# Ears_0603.net
KiCad netlist of a schematic drawn in EAGLE
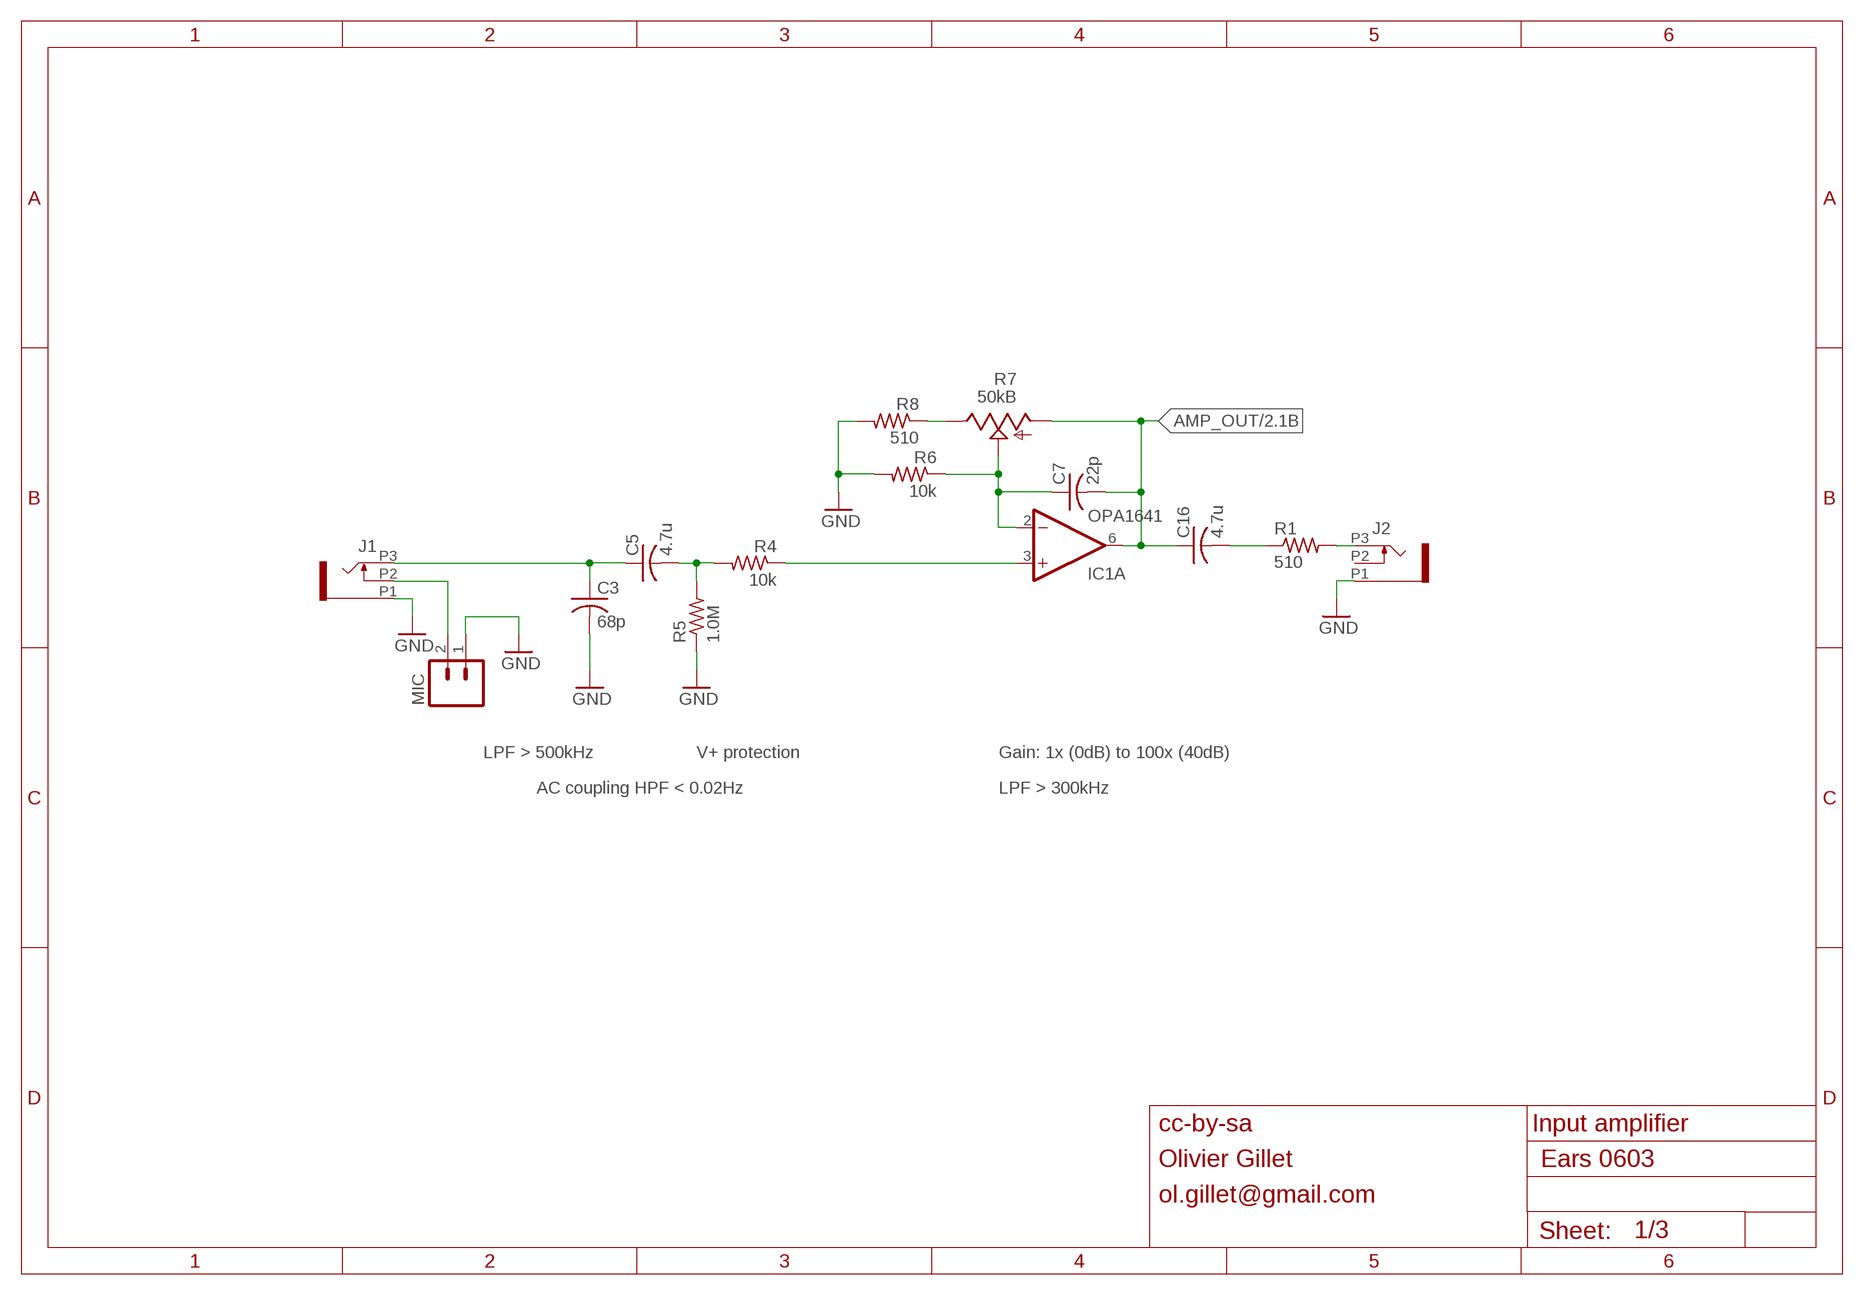
[diagram p0: schematic, sheet 1]
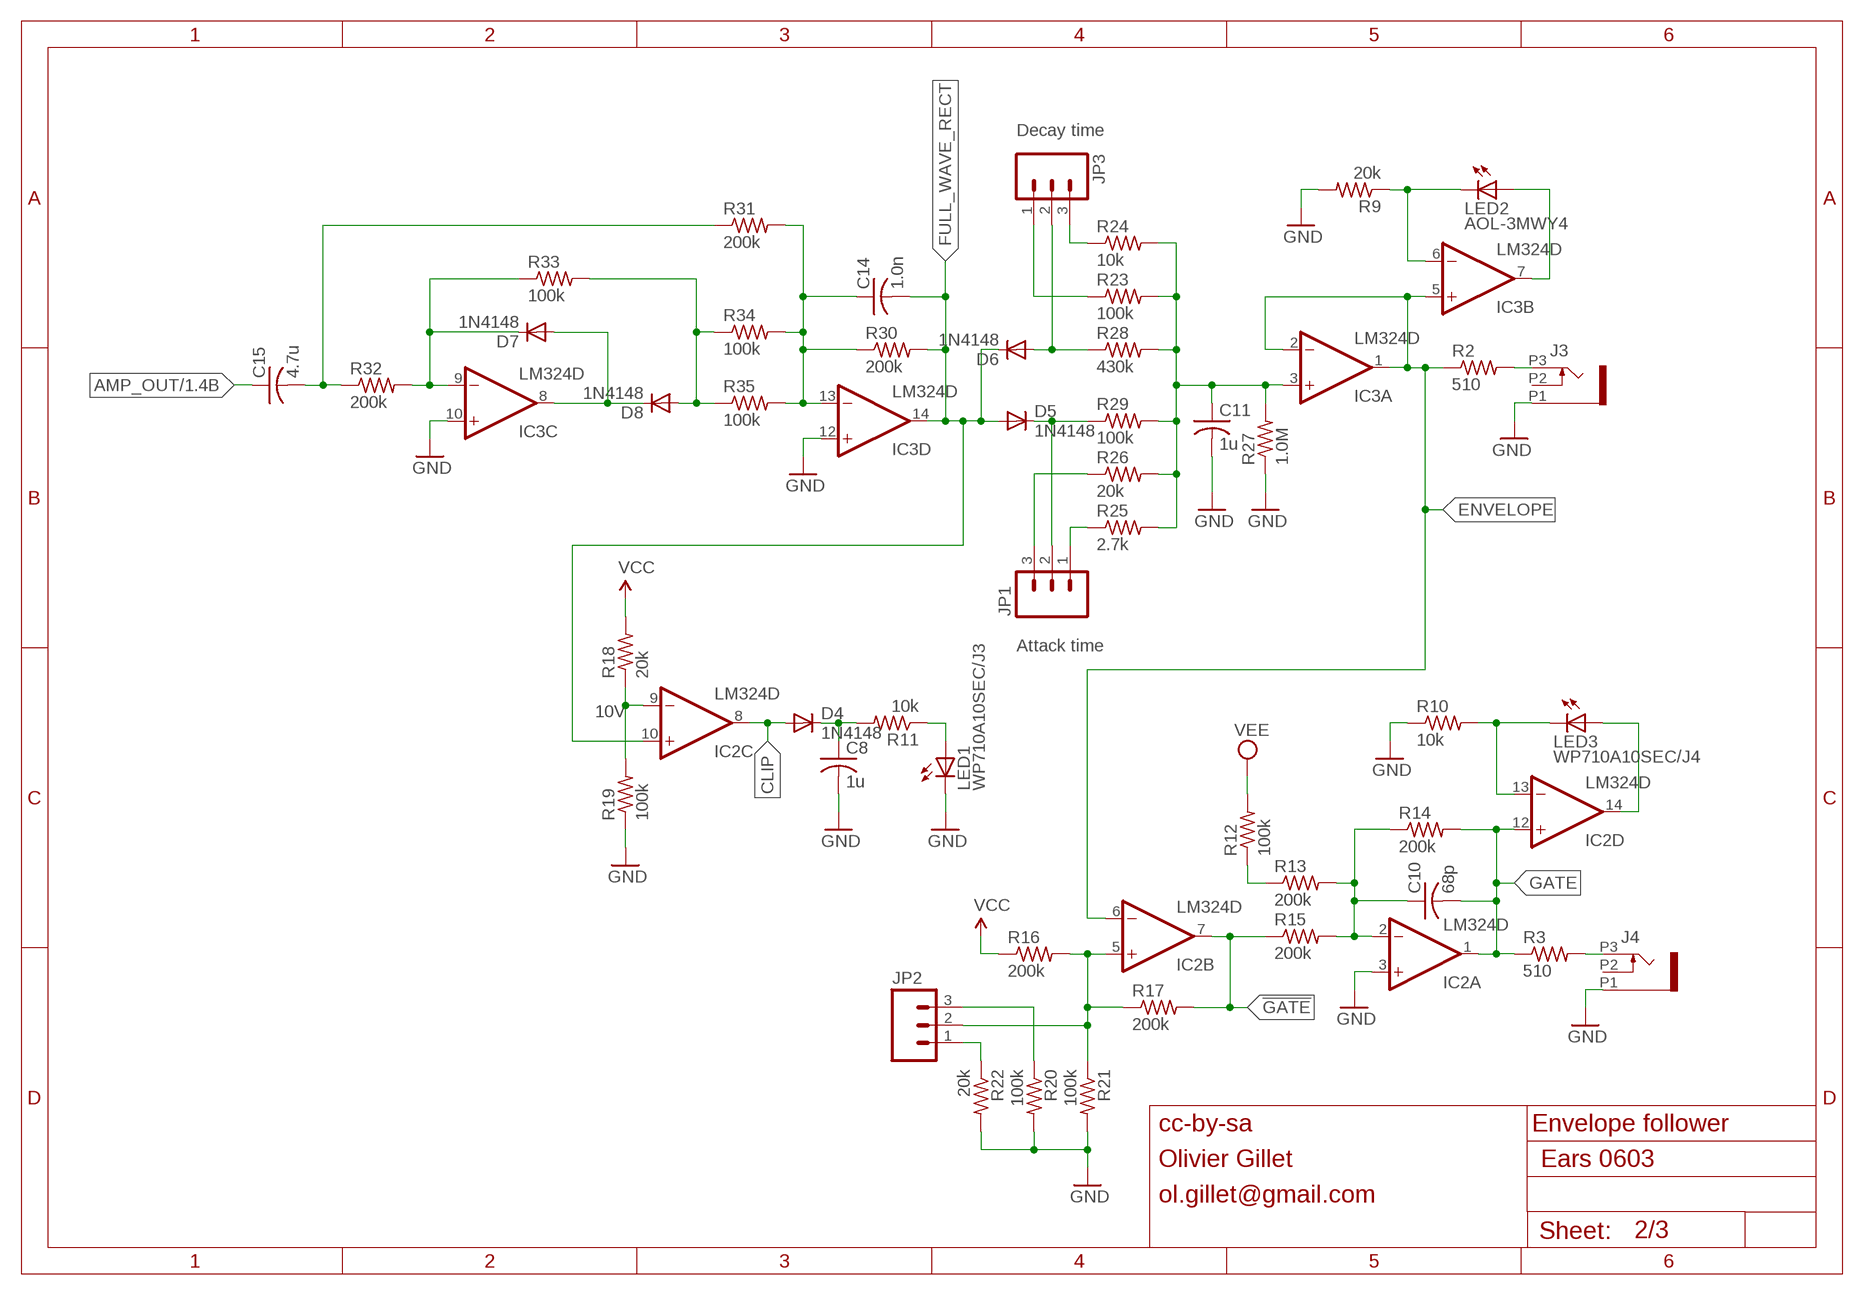
[diagram p1: schematic, sheet 2]
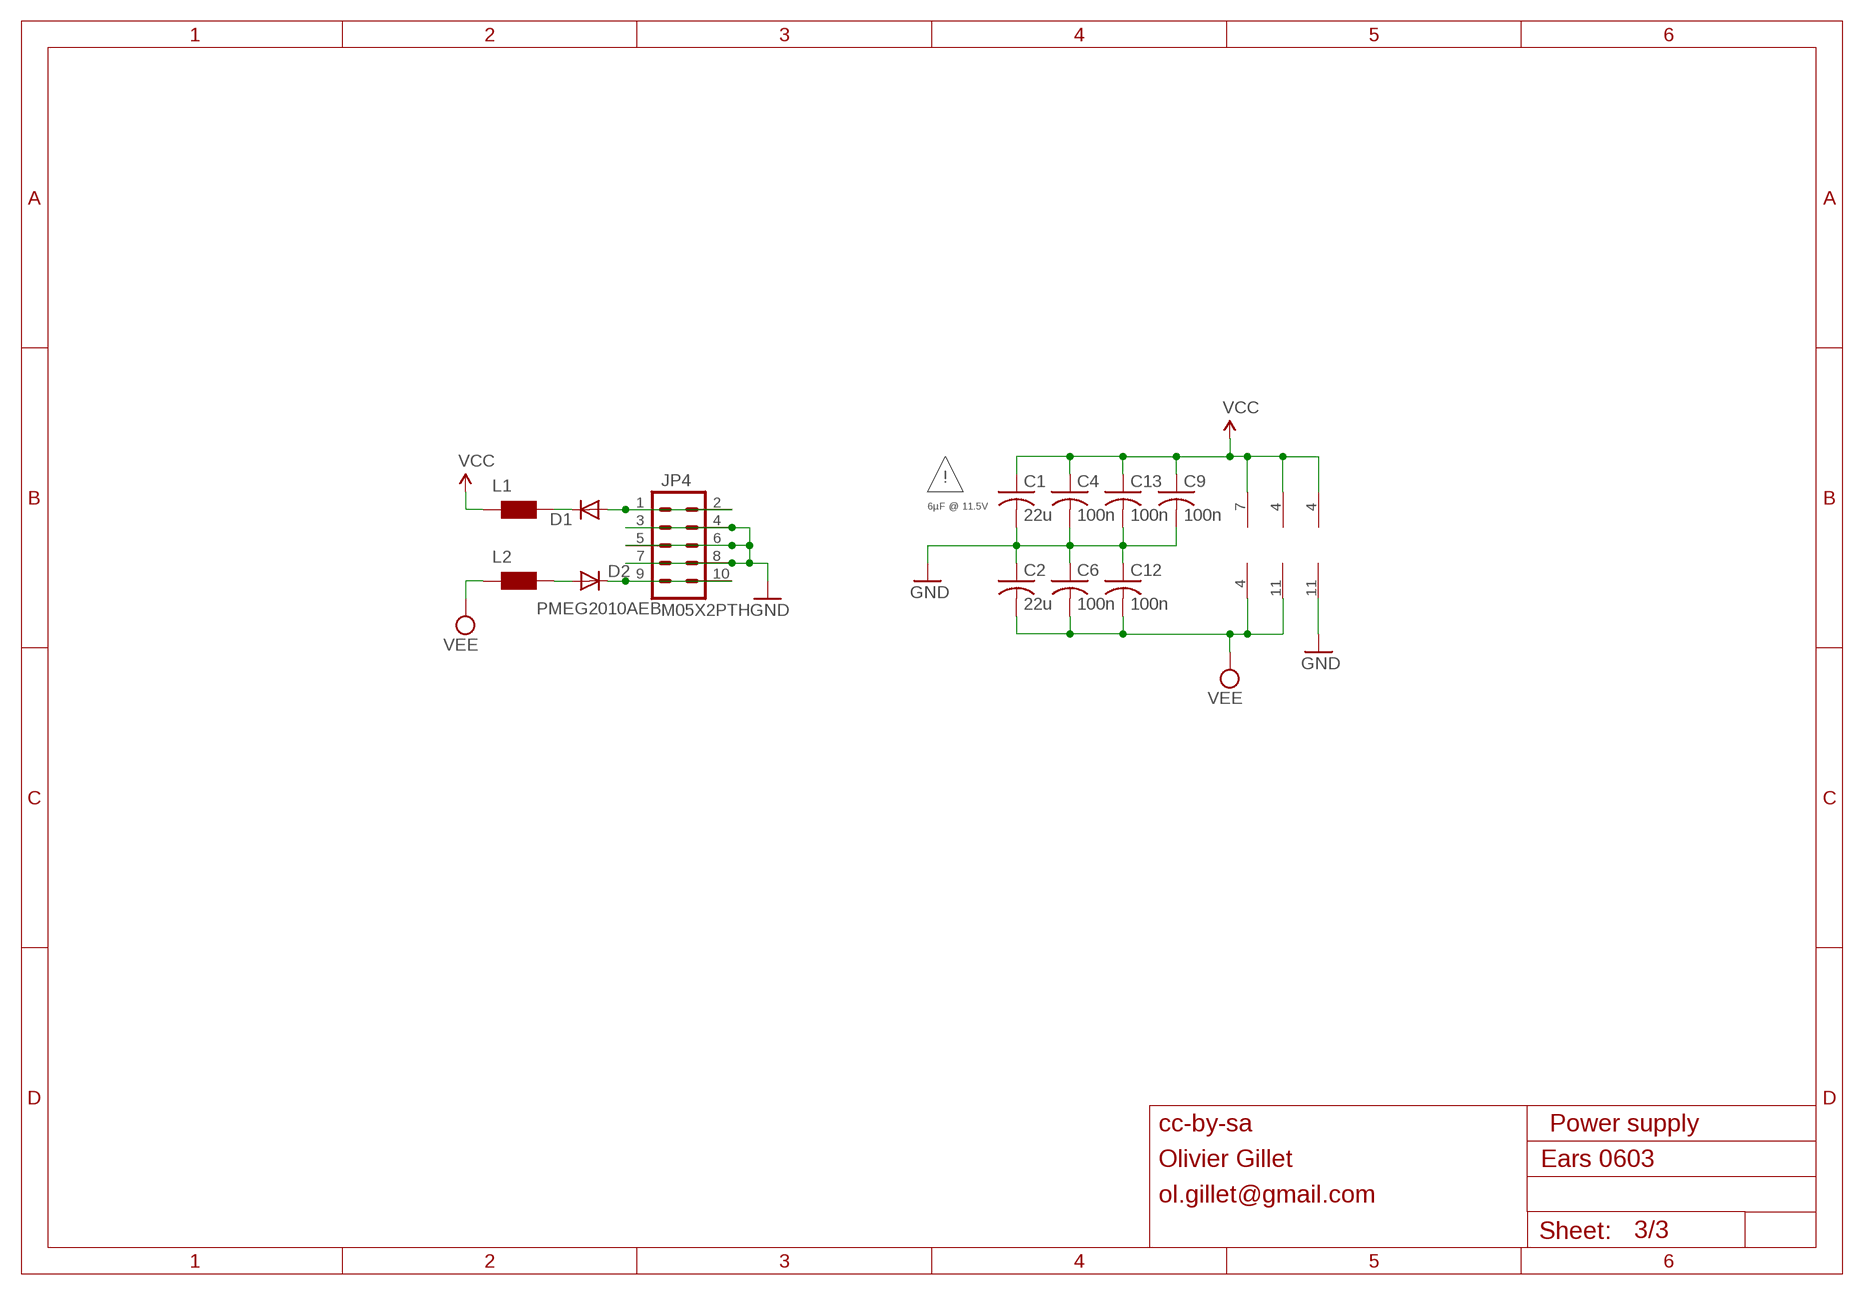
[diagram p2: schematic, sheet 3]

(export (version "E")
  (design (tool "Eeschema 10.0.6"))
  (components
    (comp (ref "C1")
      (value "22u")
      (footprint "eagle-import:C1206")
      (libsource (lib "eagle-import") (part "C-USC1206"))
    )
    (comp (ref "C2")
      (value "22u")
      (footprint "eagle-import:C1206")
      (libsource (lib "eagle-import") (part "C-USC1206"))
    )
    (comp (ref "C4")
      (value "100n")
      (footprint "eagle-import:C0603")
      (libsource (lib "eagle-import") (part "C-USC0603"))
    )
    (comp (ref "C6")
      (value "100n")
      (footprint "eagle-import:C0603")
      (libsource (lib "eagle-import") (part "C-USC0603"))
    )
    (comp (ref "C9")
      (value "100n")
      (footprint "eagle-import:C0603")
      (libsource (lib "eagle-import") (part "C-USC0603"))
    )
    (comp (ref "C12")
      (value "100n")
      (footprint "eagle-import:C0603")
      (libsource (lib "eagle-import") (part "C-USC0603"))
    )
    (comp (ref "C13")
      (value "100n")
      (footprint "eagle-import:C0603")
      (libsource (lib "eagle-import") (part "C-USC0603"))
    )
    (comp (ref "D1")
      (value "PMEG2010AEB")
      (footprint "eagle-import:SOD323-W")
      (libsource (lib "eagle-import") (part "DIODE-SOD323-W"))
    )
    (comp (ref "D2")
      (value "PMEG2010AEB")
      (footprint "eagle-import:SOD323-W")
      (libsource (lib "eagle-import") (part "DIODE-SOD323-W"))
    )
    (comp (ref "IC1")
      (value "OPA1641")
      (footprint "eagle-import:MSOP8")
      (libsource (lib "eagle-import") (part "OPA1641"))
    )
    (comp (ref "IC2")
      (value "LM324D")
      (footprint "eagle-import:SO14")
      (libsource (lib "eagle-import") (part "LM324D"))
    )
    (comp (ref "IC3")
      (value "LM324D")
      (footprint "eagle-import:SO14")
      (libsource (lib "eagle-import") (part "LM324D"))
    )
    (comp (ref "JP4")
      (value "M05X2PTH")
      (footprint "eagle-import:AVR_ICSP")
      (libsource (lib "eagle-import") (part "M05X2PTH"))
    )
    (comp (ref "L1")
      (value "WE-CBF_0603")
      (footprint "eagle-import:0603")
      (libsource (lib "eagle-import") (part "WE-CBF_0603"))
    )
    (comp (ref "L2")
      (value "WE-CBF_0603")
      (footprint "eagle-import:0603")
      (libsource (lib "eagle-import") (part "WE-CBF_0603"))
    )
    (comp (ref "C3")
      (value "68p")
      (footprint "eagle-import:C0603")
      (libsource (lib "eagle-import") (part "C-USC0603"))
    )
    (comp (ref "C5")
      (value "4.7u")
      (footprint "eagle-import:C0603")
      (libsource (lib "eagle-import") (part "C-USC0603"))
    )
    (comp (ref "C7")
      (value "22p")
      (footprint "eagle-import:C0603")
      (libsource (lib "eagle-import") (part "C-USC0603"))
    )
    (comp (ref "C16")
      (value "4.7u")
      (footprint "eagle-import:C0603")
      (libsource (lib "eagle-import") (part "C-USC0603"))
    )
    (comp (ref "J1")
      (value "PJ301_THONKICONN6")
      (footprint "eagle-import:WQP_PJ_301M6")
      (libsource (lib "eagle-import") (part "PJ301_THONKICONN6"))
    )
    (comp (ref "J2")
      (value "PJ301_THONKICONN6")
      (footprint "eagle-import:WQP_PJ_301M6")
      (libsource (lib "eagle-import") (part "PJ301_THONKICONN6"))
    )
    (comp (ref "MIC")
      (value "M02TINY")
      (footprint "eagle-import:1X02_TINY")
      (libsource (lib "eagle-import") (part "M02TINY"))
    )
    (comp (ref "R1")
      (value "510")
      (footprint "eagle-import:R0603")
      (libsource (lib "eagle-import") (part "R-US_R0603"))
    )
    (comp (ref "R4")
      (value "10k")
      (footprint "eagle-import:R0603")
      (libsource (lib "eagle-import") (part "R-US_R0603"))
    )
    (comp (ref "R5")
      (value "1.0M")
      (footprint "eagle-import:R0603")
      (libsource (lib "eagle-import") (part "R-US_R0603"))
    )
    (comp (ref "R6")
      (value "10k")
      (footprint "eagle-import:R0603")
      (libsource (lib "eagle-import") (part "R-US_R0603"))
    )
    (comp (ref "R7")
      (value "50kB")
      (footprint "eagle-import:ALPS_POT_VERTICAL_PS")
      (libsource (lib "eagle-import") (part "POT_USVERTICAL_PS"))
    )
    (comp (ref "R8")
      (value "510")
      (footprint "eagle-import:R0603")
      (libsource (lib "eagle-import") (part "R-US_R0603"))
    )
    (comp (ref "C8")
      (value "1u")
      (footprint "eagle-import:C0603")
      (libsource (lib "eagle-import") (part "C-USC0603"))
    )
    (comp (ref "C10")
      (value "68p")
      (footprint "eagle-import:C0603")
      (libsource (lib "eagle-import") (part "C-USC0603"))
    )
    (comp (ref "C11")
      (value "1u")
      (footprint "eagle-import:C0603")
      (libsource (lib "eagle-import") (part "C-USC0603"))
    )
    (comp (ref "C14")
      (value "1.0n")
      (footprint "eagle-import:C0603")
      (libsource (lib "eagle-import") (part "C-USC0603"))
    )
    (comp (ref "C15")
      (value "4.7u")
      (footprint "eagle-import:C0603")
      (libsource (lib "eagle-import") (part "C-USC0603"))
    )
    (comp (ref "D4")
      (value "1N4148")
      (footprint "eagle-import:SOD323-W")
      (libsource (lib "eagle-import") (part "DIODE-SOD323-W"))
    )
    (comp (ref "D5")
      (value "1N4148")
      (footprint "eagle-import:SOD323-W")
      (libsource (lib "eagle-import") (part "DIODE-SOD323-W"))
    )
    (comp (ref "D6")
      (value "1N4148")
      (footprint "eagle-import:SOD323-W")
      (libsource (lib "eagle-import") (part "DIODE-SOD323-W"))
    )
    (comp (ref "D7")
      (value "1N4148")
      (footprint "eagle-import:SOD323-W")
      (libsource (lib "eagle-import") (part "DIODE-SOD323-W"))
    )
    (comp (ref "D8")
      (value "1N4148")
      (footprint "eagle-import:SOD323-W")
      (libsource (lib "eagle-import") (part "DIODE-SOD323-W"))
    )
    (comp (ref "J3")
      (value "PJ301_THONKICONN6")
      (footprint "eagle-import:WQP_PJ_301M6")
      (libsource (lib "eagle-import") (part "PJ301_THONKICONN6"))
    )
    (comp (ref "J4")
      (value "PJ301_THONKICONN6")
      (footprint "eagle-import:WQP_PJ_301M6")
      (libsource (lib "eagle-import") (part "PJ301_THONKICONN6"))
    )
    (comp (ref "JP1")
      (value "M03PTH")
      (footprint "eagle-import:1X03")
      (libsource (lib "eagle-import") (part "M03PTH"))
    )
    (comp (ref "JP2")
      (value "M03PTH")
      (footprint "eagle-import:1X03")
      (libsource (lib "eagle-import") (part "M03PTH"))
    )
    (comp (ref "JP3")
      (value "M03PTH")
      (footprint "eagle-import:1X03")
      (libsource (lib "eagle-import") (part "M03PTH"))
    )
    (comp (ref "LED1")
      (value "WP710A10SEC/J3")
      (footprint "eagle-import:LED3MM")
      (libsource (lib "eagle-import") (part "LED3MM"))
    )
    (comp (ref "LED2")
      (value "AOL-3MWY4")
      (footprint "eagle-import:LED3MM")
      (libsource (lib "eagle-import") (part "LED3MM"))
    )
    (comp (ref "LED3")
      (value "WP710A10SEC/J4")
      (footprint "eagle-import:LED3MM")
      (libsource (lib "eagle-import") (part "LED3MM"))
    )
    (comp (ref "R2")
      (value "510")
      (footprint "eagle-import:R0603")
      (libsource (lib "eagle-import") (part "R-US_R0603"))
    )
    (comp (ref "R3")
      (value "510")
      (footprint "eagle-import:R0603")
      (libsource (lib "eagle-import") (part "R-US_R0603"))
    )
    (comp (ref "R9")
      (value "20k")
      (footprint "eagle-import:R0603")
      (libsource (lib "eagle-import") (part "R-US_R0603"))
    )
    (comp (ref "R10")
      (value "10k")
      (footprint "eagle-import:R0603")
      (libsource (lib "eagle-import") (part "R-US_R0603"))
    )
    (comp (ref "R11")
      (value "10k")
      (footprint "eagle-import:R0603")
      (libsource (lib "eagle-import") (part "R-US_R0603"))
    )
    (comp (ref "R12")
      (value "100k")
      (footprint "eagle-import:R0603")
      (libsource (lib "eagle-import") (part "R-US_R0603"))
    )
    (comp (ref "R13")
      (value "200k")
      (footprint "eagle-import:R0603")
      (libsource (lib "eagle-import") (part "R-US_R0603"))
    )
    (comp (ref "R14")
      (value "200k")
      (footprint "eagle-import:R0603")
      (libsource (lib "eagle-import") (part "R-US_R0603"))
    )
    (comp (ref "R15")
      (value "200k")
      (footprint "eagle-import:R0603")
      (libsource (lib "eagle-import") (part "R-US_R0603"))
    )
    (comp (ref "R16")
      (value "200k")
      (footprint "eagle-import:R0603")
      (libsource (lib "eagle-import") (part "R-US_R0603"))
    )
    (comp (ref "R17")
      (value "200k")
      (footprint "eagle-import:R0603")
      (libsource (lib "eagle-import") (part "R-US_R0603"))
    )
    (comp (ref "R18")
      (value "20k")
      (footprint "eagle-import:R0603")
      (libsource (lib "eagle-import") (part "R-US_R0603"))
    )
    (comp (ref "R19")
      (value "100k")
      (footprint "eagle-import:R0603")
      (libsource (lib "eagle-import") (part "R-US_R0603"))
    )
    (comp (ref "R20")
      (value "100k")
      (footprint "eagle-import:R0603")
      (libsource (lib "eagle-import") (part "R-US_R0603"))
    )
    (comp (ref "R21")
      (value "100k")
      (footprint "eagle-import:R0603")
      (libsource (lib "eagle-import") (part "R-US_R0603"))
    )
    (comp (ref "R22")
      (value "20k")
      (footprint "eagle-import:R0603")
      (libsource (lib "eagle-import") (part "R-US_R0603"))
    )
    (comp (ref "R23")
      (value "100k")
      (footprint "eagle-import:R0603")
      (libsource (lib "eagle-import") (part "R-US_R0603"))
    )
    (comp (ref "R24")
      (value "10k")
      (footprint "eagle-import:R0603")
      (libsource (lib "eagle-import") (part "R-US_R0603"))
    )
    (comp (ref "R25")
      (value "2.7k")
      (footprint "eagle-import:R0603")
      (libsource (lib "eagle-import") (part "R-US_R0603"))
    )
    (comp (ref "R26")
      (value "20k")
      (footprint "eagle-import:R0603")
      (libsource (lib "eagle-import") (part "R-US_R0603"))
    )
    (comp (ref "R27")
      (value "1.0M")
      (footprint "eagle-import:R0603")
      (libsource (lib "eagle-import") (part "R-US_R0603"))
    )
    (comp (ref "R28")
      (value "430k")
      (footprint "eagle-import:R0603")
      (libsource (lib "eagle-import") (part "R-US_R0603"))
    )
    (comp (ref "R29")
      (value "100k")
      (footprint "eagle-import:R0603")
      (libsource (lib "eagle-import") (part "R-US_R0603"))
    )
    (comp (ref "R30")
      (value "200k")
      (footprint "eagle-import:R0603")
      (libsource (lib "eagle-import") (part "R-US_R0603"))
    )
    (comp (ref "R31")
      (value "200k")
      (footprint "eagle-import:R0603")
      (libsource (lib "eagle-import") (part "R-US_R0603"))
    )
    (comp (ref "R32")
      (value "200k")
      (footprint "eagle-import:R0603")
      (libsource (lib "eagle-import") (part "R-US_R0603"))
    )
    (comp (ref "R33")
      (value "100k")
      (footprint "eagle-import:R0603")
      (libsource (lib "eagle-import") (part "R-US_R0603"))
    )
    (comp (ref "R34")
      (value "100k")
      (footprint "eagle-import:R0603")
      (libsource (lib "eagle-import") (part "R-US_R0603"))
    )
    (comp (ref "R35")
      (value "100k")
      (footprint "eagle-import:R0603")
      (libsource (lib "eagle-import") (part "R-US_R0603"))
    )
  )
  (nets
    (net (code "1") (name "AMP_OUT") (class "Default")
      (node (ref "C15") (pin "1") (pinfunction "1_1") (pintype "passive"))
      (node (ref "C16") (pin "1") (pinfunction "1_1") (pintype "passive"))
      (node (ref "C7") (pin "2") (pinfunction "2_2") (pintype "passive"))
      (node (ref "IC1") (pin "6") (pinfunction "OUT_6") (pintype "output"))
      (node (ref "R7") (pin "P$3") (pinfunction "A_P$3") (pintype "passive"))
    )
    (net (code "2") (name "CLIP") (class "Default")
      (node (ref "D4") (pin "A") (pinfunction "A_A") (pintype "passive"))
      (node (ref "IC2") (pin "8") (pinfunction "OUT_8") (pintype "output"))
    )
    (net (code "3") (name "ENVELOPE") (class "Default")
      (node (ref "IC2") (pin "6") (pinfunction "-IN_6") (pintype "input"))
      (node (ref "IC3") (pin "1") (pinfunction "OUT_1") (pintype "output"))
      (node (ref "IC3") (pin "2") (pinfunction "-IN_2") (pintype "input"))
      (node (ref "IC3") (pin "5") (pinfunction "+IN_5") (pintype "input"))
      (node (ref "R2") (pin "1") (pinfunction "1_1") (pintype "passive"))
    )
    (net (code "4") (name "FULL_WAVE_RECT") (class "Default")
      (node (ref "C14") (pin "2") (pinfunction "2_2") (pintype "passive"))
      (node (ref "D5") (pin "A") (pinfunction "A_A") (pintype "passive"))
      (node (ref "D6") (pin "C") (pinfunction "C_C") (pintype "passive"))
      (node (ref "IC2") (pin "10") (pinfunction "+IN_10") (pintype "input"))
      (node (ref "IC3") (pin "14") (pinfunction "OUT_14") (pintype "output"))
      (node (ref "R30") (pin "2") (pinfunction "2_2") (pintype "passive"))
    )
    (net (code "5") (name "GATE") (class "Default")
      (node (ref "C10") (pin "2") (pinfunction "2_2") (pintype "passive"))
      (node (ref "IC2") (pin "1") (pinfunction "OUT_1") (pintype "output"))
      (node (ref "IC2") (pin "12") (pinfunction "+IN_12") (pintype "input"))
      (node (ref "R14") (pin "2") (pinfunction "2_2") (pintype "passive"))
      (node (ref "R3") (pin "1") (pinfunction "1_1") (pintype "passive"))
    )
    (net (code "6") (name "GND") (class "Default")
      (node (ref "C1") (pin "2") (pinfunction "2_2") (pintype "passive"))
      (node (ref "C11") (pin "2") (pinfunction "2_2") (pintype "passive"))
      (node (ref "C12") (pin "1") (pinfunction "1_1") (pintype "passive"))
      (node (ref "C13") (pin "2") (pinfunction "2_2") (pintype "passive"))
      (node (ref "C2") (pin "1") (pinfunction "1_1") (pintype "passive"))
      (node (ref "C3") (pin "2") (pinfunction "2_2") (pintype "passive"))
      (node (ref "C4") (pin "2") (pinfunction "2_2") (pintype "passive"))
      (node (ref "C6") (pin "1") (pinfunction "1_1") (pintype "passive"))
      (node (ref "C8") (pin "2") (pinfunction "2_2") (pintype "passive"))
      (node (ref "C9") (pin "2") (pinfunction "2_2") (pintype "passive"))
      (node (ref "IC2") (pin "11") (pinfunction "V-_11") (pintype "power_in"))
      (node (ref "IC2") (pin "3") (pinfunction "+IN_3") (pintype "input"))
      (node (ref "IC3") (pin "10") (pinfunction "+IN_10") (pintype "input"))
      (node (ref "IC3") (pin "12") (pinfunction "+IN_12") (pintype "input"))
      (node (ref "J1") (pin "P1") (pinfunction "1_P1") (pintype "passive"))
      (node (ref "J2") (pin "P1") (pinfunction "1_P1") (pintype "passive"))
      (node (ref "J3") (pin "P1") (pinfunction "1_P1") (pintype "passive"))
      (node (ref "J4") (pin "P1") (pinfunction "1_P1") (pintype "passive"))
      (node (ref "JP4") (pin "3") (pinfunction "3_3") (pintype "passive"))
      (node (ref "JP4") (pin "4") (pinfunction "4_4") (pintype "passive"))
      (node (ref "JP4") (pin "5") (pinfunction "5_5") (pintype "passive"))
      (node (ref "JP4") (pin "6") (pinfunction "6_6") (pintype "passive"))
      (node (ref "JP4") (pin "7") (pinfunction "7_7") (pintype "passive"))
      (node (ref "JP4") (pin "8") (pinfunction "8_8") (pintype "passive"))
      (node (ref "LED1") (pin "K") (pinfunction "C_K") (pintype "passive"))
      (node (ref "MIC") (pin "1") (pinfunction "1_1") (pintype "passive"))
      (node (ref "R10") (pin "1") (pinfunction "1_1") (pintype "passive"))
      (node (ref "R19") (pin "1") (pinfunction "1_1") (pintype "passive"))
      (node (ref "R20") (pin "2") (pinfunction "2_2") (pintype "passive"))
      (node (ref "R21") (pin "2") (pinfunction "2_2") (pintype "passive"))
      (node (ref "R22") (pin "2") (pinfunction "2_2") (pintype "passive"))
      (node (ref "R27") (pin "1") (pinfunction "1_1") (pintype "passive"))
      (node (ref "R5") (pin "1") (pinfunction "1_1") (pintype "passive"))
      (node (ref "R6") (pin "2") (pinfunction "2_2") (pintype "passive"))
      (node (ref "R8") (pin "2") (pinfunction "2_2") (pintype "passive"))
      (node (ref "R9") (pin "2") (pinfunction "2_2") (pintype "passive"))
    )
    (net (code "7") (name "Net-(C5-Pad2)") (class "Default")
      (node (ref "C5") (pin "2") (pinfunction "2_2") (pintype "passive"))
      (node (ref "R4") (pin "2") (pinfunction "2_2") (pintype "passive"))
      (node (ref "R5") (pin "2") (pinfunction "2_2") (pintype "passive"))
    )
    (net (code "8") (name "Net-(C8-Pad1)") (class "Default")
      (node (ref "C8") (pin "1") (pinfunction "1_1") (pintype "passive"))
      (node (ref "D4") (pin "C") (pinfunction "C_C") (pintype "passive"))
      (node (ref "R11") (pin "2") (pinfunction "2_2") (pintype "passive"))
    )
    (net (code "9") (name "Net-(C15-Pad2)") (class "Default")
      (node (ref "C15") (pin "2") (pinfunction "2_2") (pintype "passive"))
      (node (ref "R31") (pin "1") (pinfunction "1_1") (pintype "passive"))
      (node (ref "R32") (pin "1") (pinfunction "1_1") (pintype "passive"))
    )
    (net (code "10") (name "Net-(C16-Pad2)") (class "Default")
      (node (ref "C16") (pin "2") (pinfunction "2_2") (pintype "passive"))
      (node (ref "R1") (pin "1") (pinfunction "1_1") (pintype "passive"))
    )
    (net (code "11") (name "Net-(D1-PadA)") (class "Default")
      (node (ref "D1") (pin "A") (pinfunction "A_A") (pintype "passive"))
      (node (ref "JP4") (pin "1") (pinfunction "1_1") (pintype "passive"))
      (node (ref "JP4") (pin "2") (pinfunction "2_2") (pintype "passive"))
    )
    (net (code "12") (name "Net-(D1-PadC)") (class "Default")
      (node (ref "D1") (pin "C") (pinfunction "C_C") (pintype "passive"))
      (node (ref "L1") (pin "2") (pinfunction "2_2") (pintype "passive"))
    )
    (net (code "13") (name "Net-(D2-PadA)") (class "Default")
      (node (ref "D2") (pin "A") (pinfunction "A_A") (pintype "passive"))
      (node (ref "L2") (pin "2") (pinfunction "2_2") (pintype "passive"))
    )
    (net (code "14") (name "Net-(D2-PadC)") (class "Default")
      (node (ref "D2") (pin "C") (pinfunction "C_C") (pintype "passive"))
      (node (ref "JP4") (pin "10") (pinfunction "10_10") (pintype "passive"))
      (node (ref "JP4") (pin "9") (pinfunction "9_9") (pintype "passive"))
    )
    (net (code "15") (name "Net-(D5-PadC)") (class "Default")
      (node (ref "D5") (pin "C") (pinfunction "C_C") (pintype "passive"))
      (node (ref "JP1") (pin "2") (pinfunction "2_2") (pintype "passive"))
      (node (ref "R29") (pin "1") (pinfunction "1_1") (pintype "passive"))
    )
    (net (code "16") (name "Net-(D6-PadA)") (class "Default")
      (node (ref "D6") (pin "A") (pinfunction "A_A") (pintype "passive"))
      (node (ref "JP3") (pin "2") (pinfunction "2_2") (pintype "passive"))
      (node (ref "R28") (pin "1") (pinfunction "1_1") (pintype "passive"))
    )
    (net (code "17") (name "Net-(D8-PadA)") (class "Default")
      (node (ref "D8") (pin "A") (pinfunction "A_A") (pintype "passive"))
      (node (ref "R33") (pin "2") (pinfunction "2_2") (pintype "passive"))
      (node (ref "R34") (pin "1") (pinfunction "1_1") (pintype "passive"))
      (node (ref "R35") (pin "1") (pinfunction "1_1") (pintype "passive"))
    )
    (net (code "18") (name "Net-(IC1A-+IN)") (class "Default")
      (node (ref "IC1") (pin "3") (pinfunction "+IN_3") (pintype "input"))
      (node (ref "R4") (pin "1") (pinfunction "1_1") (pintype "passive"))
    )
    (net (code "19") (name "Net-(IC1A--IN)") (class "Default")
      (node (ref "C7") (pin "1") (pinfunction "1_1") (pintype "passive"))
      (node (ref "IC1") (pin "2") (pinfunction "-IN_2") (pintype "input"))
      (node (ref "R6") (pin "1") (pinfunction "1_1") (pintype "passive"))
      (node (ref "R7") (pin "P$2") (pinfunction "S_P$2") (pintype "passive"))
    )
    (net (code "20") (name "Net-(IC2A--IN)") (class "Default")
      (node (ref "C10") (pin "1") (pinfunction "1_1") (pintype "passive"))
      (node (ref "IC2") (pin "2") (pinfunction "-IN_2") (pintype "input"))
      (node (ref "R13") (pin "2") (pinfunction "2_2") (pintype "passive"))
      (node (ref "R14") (pin "1") (pinfunction "1_1") (pintype "passive"))
      (node (ref "R15") (pin "2") (pinfunction "2_2") (pintype "passive"))
    )
    (net (code "21") (name "Net-(IC2B-+IN)") (class "Default")
      (node (ref "IC2") (pin "5") (pinfunction "+IN_5") (pintype "input"))
      (node (ref "JP2") (pin "2") (pinfunction "2_2") (pintype "passive"))
      (node (ref "R16") (pin "2") (pinfunction "2_2") (pintype "passive"))
      (node (ref "R17") (pin "1") (pinfunction "1_1") (pintype "passive"))
      (node (ref "R21") (pin "1") (pinfunction "1_1") (pintype "passive"))
    )
    (net (code "22") (name "Net-(IC2C--IN)") (class "Default")
      (node (ref "IC2") (pin "9") (pinfunction "-IN_9") (pintype "input"))
      (node (ref "R18") (pin "1") (pinfunction "1_1") (pintype "passive"))
      (node (ref "R19") (pin "2") (pinfunction "2_2") (pintype "passive"))
    )
    (net (code "23") (name "Net-(IC2D--IN)") (class "Default")
      (node (ref "IC2") (pin "13") (pinfunction "-IN_13") (pintype "input"))
      (node (ref "LED3") (pin "K") (pinfunction "C_K") (pintype "passive"))
      (node (ref "R10") (pin "2") (pinfunction "2_2") (pintype "passive"))
    )
    (net (code "24") (name "Net-(IC2D-OUT)") (class "Default")
      (node (ref "IC2") (pin "14") (pinfunction "OUT_14") (pintype "output"))
      (node (ref "LED3") (pin "A") (pinfunction "A_A") (pintype "passive"))
    )
    (net (code "25") (name "Net-(IC3A-+IN)") (class "Default")
      (node (ref "C11") (pin "1") (pinfunction "1_1") (pintype "passive"))
      (node (ref "IC3") (pin "3") (pinfunction "+IN_3") (pintype "input"))
      (node (ref "R23") (pin "2") (pinfunction "2_2") (pintype "passive"))
      (node (ref "R24") (pin "2") (pinfunction "2_2") (pintype "passive"))
      (node (ref "R25") (pin "2") (pinfunction "2_2") (pintype "passive"))
      (node (ref "R26") (pin "2") (pinfunction "2_2") (pintype "passive"))
      (node (ref "R27") (pin "2") (pinfunction "2_2") (pintype "passive"))
      (node (ref "R28") (pin "2") (pinfunction "2_2") (pintype "passive"))
      (node (ref "R29") (pin "2") (pinfunction "2_2") (pintype "passive"))
    )
    (net (code "26") (name "Net-(IC3B--IN)") (class "Default")
      (node (ref "IC3") (pin "6") (pinfunction "-IN_6") (pintype "input"))
      (node (ref "LED2") (pin "K") (pinfunction "C_K") (pintype "passive"))
      (node (ref "R9") (pin "1") (pinfunction "1_1") (pintype "passive"))
    )
    (net (code "27") (name "Net-(IC3B-OUT)") (class "Default")
      (node (ref "IC3") (pin "7") (pinfunction "OUT_7") (pintype "output"))
      (node (ref "LED2") (pin "A") (pinfunction "A_A") (pintype "passive"))
    )
    (net (code "28") (name "Net-(IC3C--IN)") (class "Default")
      (node (ref "D7") (pin "C") (pinfunction "C_C") (pintype "passive"))
      (node (ref "IC3") (pin "9") (pinfunction "-IN_9") (pintype "input"))
      (node (ref "R32") (pin "2") (pinfunction "2_2") (pintype "passive"))
      (node (ref "R33") (pin "1") (pinfunction "1_1") (pintype "passive"))
    )
    (net (code "29") (name "Net-(IC3C-OUT)") (class "Default")
      (node (ref "D7") (pin "A") (pinfunction "A_A") (pintype "passive"))
      (node (ref "D8") (pin "C") (pinfunction "C_C") (pintype "passive"))
      (node (ref "IC3") (pin "8") (pinfunction "OUT_8") (pintype "output"))
    )
    (net (code "30") (name "Net-(IC3D--IN)") (class "Default")
      (node (ref "C14") (pin "1") (pinfunction "1_1") (pintype "passive"))
      (node (ref "IC3") (pin "13") (pinfunction "-IN_13") (pintype "input"))
      (node (ref "R30") (pin "1") (pinfunction "1_1") (pintype "passive"))
      (node (ref "R31") (pin "2") (pinfunction "2_2") (pintype "passive"))
      (node (ref "R34") (pin "2") (pinfunction "2_2") (pintype "passive"))
      (node (ref "R35") (pin "2") (pinfunction "2_2") (pintype "passive"))
    )
    (net (code "31") (name "Net-(J1-2)") (class "Default")
      (node (ref "J1") (pin "P2") (pinfunction "2_P2") (pintype "passive"))
      (node (ref "MIC") (pin "2") (pinfunction "2_2") (pintype "passive"))
    )
    (net (code "32") (name "Net-(J1-3)") (class "Default")
      (node (ref "C3") (pin "1") (pinfunction "1_1") (pintype "passive"))
      (node (ref "C5") (pin "1") (pinfunction "1_1") (pintype "passive"))
      (node (ref "J1") (pin "P3") (pinfunction "3_P3") (pintype "passive"))
    )
    (net (code "33") (name "Net-(J2-3)") (class "Default")
      (node (ref "J2") (pin "P3") (pinfunction "3_P3") (pintype "passive"))
      (node (ref "R1") (pin "2") (pinfunction "2_2") (pintype "passive"))
    )
    (net (code "34") (name "Net-(J3-3)") (class "Default")
      (node (ref "J3") (pin "P3") (pinfunction "3_P3") (pintype "passive"))
      (node (ref "R2") (pin "2") (pinfunction "2_2") (pintype "passive"))
    )
    (net (code "35") (name "Net-(J4-3)") (class "Default")
      (node (ref "J4") (pin "P3") (pinfunction "3_P3") (pintype "passive"))
      (node (ref "R3") (pin "2") (pinfunction "2_2") (pintype "passive"))
    )
    (net (code "36") (name "Net-(JP1-Pad1)") (class "Default")
      (node (ref "JP1") (pin "1") (pinfunction "1_1") (pintype "passive"))
      (node (ref "R25") (pin "1") (pinfunction "1_1") (pintype "passive"))
    )
    (net (code "37") (name "Net-(JP1-Pad3)") (class "Default")
      (node (ref "JP1") (pin "3") (pinfunction "3_3") (pintype "passive"))
      (node (ref "R26") (pin "1") (pinfunction "1_1") (pintype "passive"))
    )
    (net (code "38") (name "Net-(JP2-Pad1)") (class "Default")
      (node (ref "JP2") (pin "1") (pinfunction "1_1") (pintype "passive"))
      (node (ref "R22") (pin "1") (pinfunction "1_1") (pintype "passive"))
    )
    (net (code "39") (name "Net-(JP2-Pad3)") (class "Default")
      (node (ref "JP2") (pin "3") (pinfunction "3_3") (pintype "passive"))
      (node (ref "R20") (pin "1") (pinfunction "1_1") (pintype "passive"))
    )
    (net (code "40") (name "Net-(JP3-Pad1)") (class "Default")
      (node (ref "JP3") (pin "1") (pinfunction "1_1") (pintype "passive"))
      (node (ref "R23") (pin "1") (pinfunction "1_1") (pintype "passive"))
    )
    (net (code "41") (name "Net-(JP3-Pad3)") (class "Default")
      (node (ref "JP3") (pin "3") (pinfunction "3_3") (pintype "passive"))
      (node (ref "R24") (pin "1") (pinfunction "1_1") (pintype "passive"))
    )
    (net (code "42") (name "Net-(LED1-PadA)") (class "Default")
      (node (ref "LED1") (pin "A") (pinfunction "A_A") (pintype "passive"))
      (node (ref "R11") (pin "1") (pinfunction "1_1") (pintype "passive"))
    )
    (net (code "43") (name "Net-(R7-E)") (class "Default")
      (node (ref "R7") (pin "P$1") (pinfunction "E_P$1") (pintype "passive"))
      (node (ref "R8") (pin "1") (pinfunction "1_1") (pintype "passive"))
    )
    (net (code "44") (name "Net-(R12-Pad1)") (class "Default")
      (node (ref "R12") (pin "1") (pinfunction "1_1") (pintype "passive"))
      (node (ref "R13") (pin "1") (pinfunction "1_1") (pintype "passive"))
    )
    (net (code "45") (name "VCC") (class "Default")
      (node (ref "C1") (pin "1") (pinfunction "1_1") (pintype "passive"))
      (node (ref "C13") (pin "1") (pinfunction "1_1") (pintype "passive"))
      (node (ref "C4") (pin "1") (pinfunction "1_1") (pintype "passive"))
      (node (ref "C9") (pin "1") (pinfunction "1_1") (pintype "passive"))
      (node (ref "IC1") (pin "7") (pinfunction "V+_7") (pintype "power_in"))
      (node (ref "IC2") (pin "4") (pinfunction "V+_4") (pintype "power_in"))
      (node (ref "IC3") (pin "4") (pinfunction "V+_4") (pintype "power_in"))
      (node (ref "L1") (pin "1") (pinfunction "1_1") (pintype "passive"))
      (node (ref "R16") (pin "1") (pinfunction "1_1") (pintype "passive"))
      (node (ref "R18") (pin "2") (pinfunction "2_2") (pintype "passive"))
    )
    (net (code "46") (name "VEE") (class "Default")
      (node (ref "C12") (pin "2") (pinfunction "2_2") (pintype "passive"))
      (node (ref "C2") (pin "2") (pinfunction "2_2") (pintype "passive"))
      (node (ref "C6") (pin "2") (pinfunction "2_2") (pintype "passive"))
      (node (ref "IC1") (pin "4") (pinfunction "V-_4") (pintype "power_in"))
      (node (ref "IC3") (pin "11") (pinfunction "V-_11") (pintype "power_in"))
      (node (ref "L2") (pin "1") (pinfunction "1_1") (pintype "passive"))
      (node (ref "R12") (pin "2") (pinfunction "2_2") (pintype "passive"))
    )
    (net (code "47") (name "unconnected-(J2-2-PadP2)") (class "Default")
      (node (ref "J2") (pin "P2") (pinfunction "2_P2") (pintype "passive"))
    )
    (net (code "48") (name "unconnected-(J3-2-PadP2)") (class "Default")
      (node (ref "J3") (pin "P2") (pinfunction "2_P2") (pintype "passive"))
    )
    (net (code "49") (name "unconnected-(J4-2-PadP2)") (class "Default")
      (node (ref "J4") (pin "P2") (pinfunction "2_P2") (pintype "passive"))
    )
    (net (code "50") (name "~{GATE}") (class "Default")
      (node (ref "IC2") (pin "7") (pinfunction "OUT_7") (pintype "output"))
      (node (ref "R15") (pin "1") (pinfunction "1_1") (pintype "passive"))
      (node (ref "R17") (pin "2") (pinfunction "2_2") (pintype "passive"))
    )
  )
)
